# EVK-IRIS-W1-PIN-HEADERS_SDIO-HEADER.net
KiCad netlist of a schematic drawn in Altium Designer
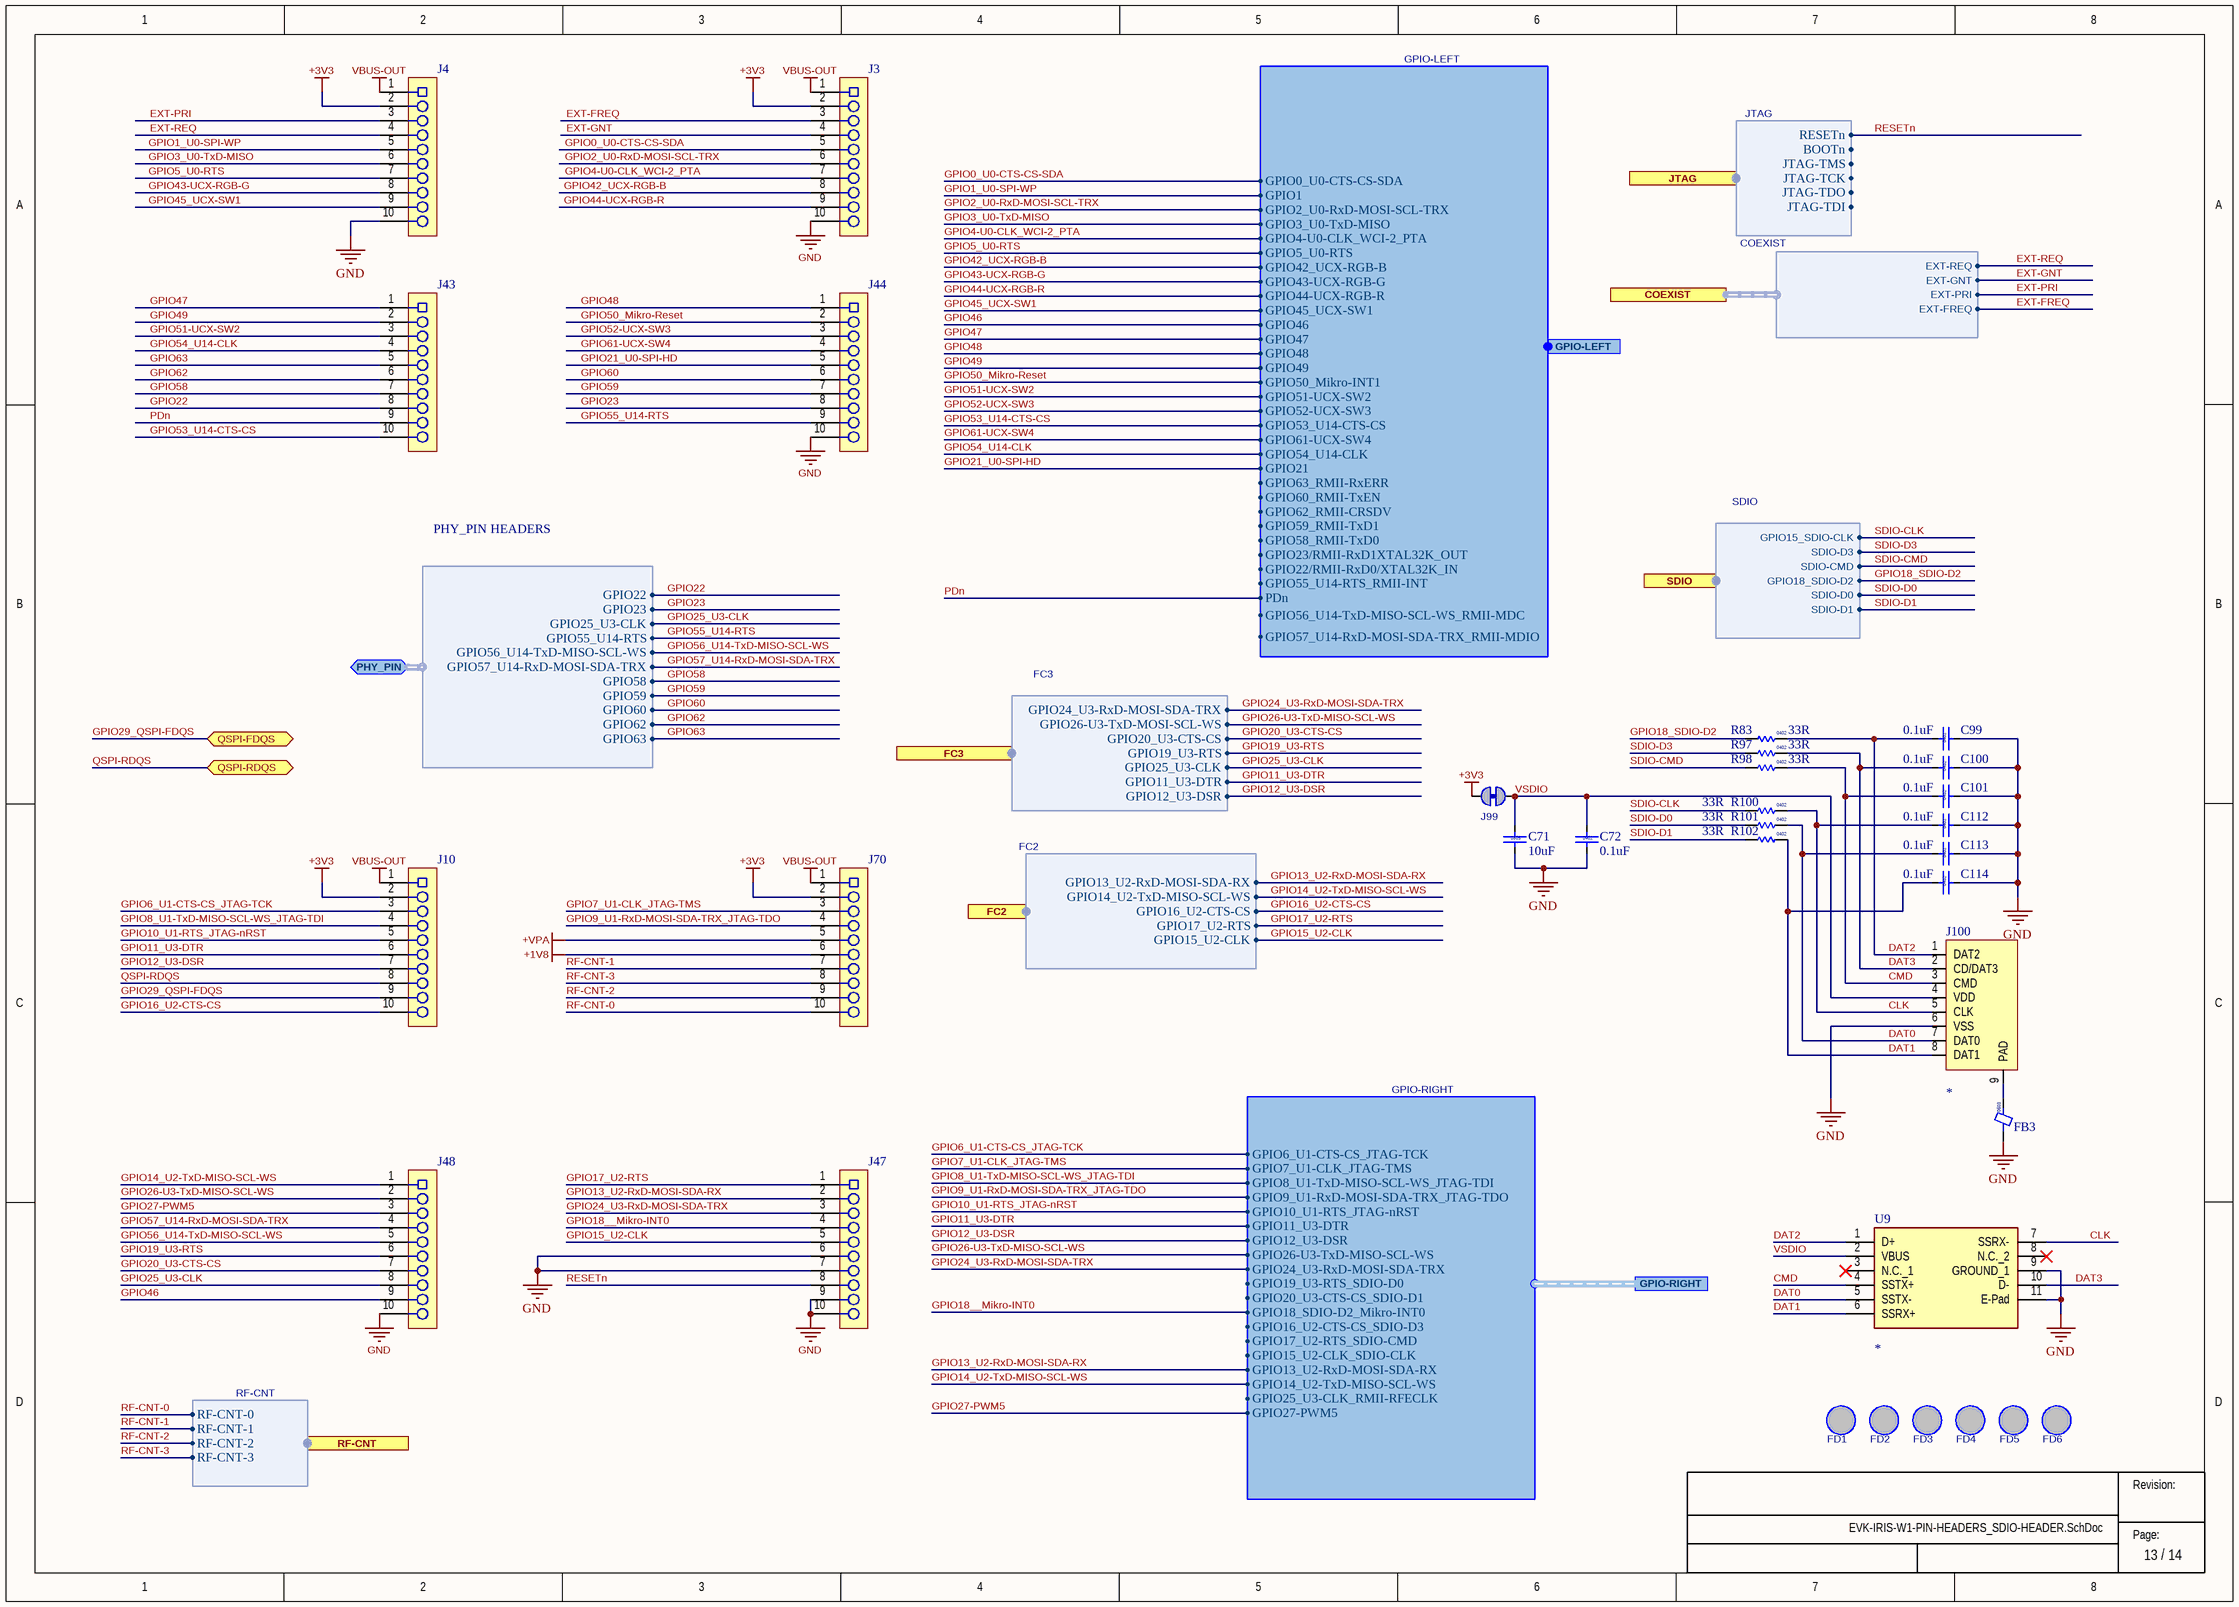
[diagram p0: EVK-IRIS-W1-PIN-HEADERS_SDIO-HEADER.SchDoc]

(export (version "E")
  (design (tool "Eeschema 10.0.6"))
  (components
    (comp (ref "C71")
      (value "10uF")
      (footprint "Cap 0805 HD")
      (description "Capacitor, Ceramic, 10uF 16V 10% X7R, 0805")
      (fields
        (field (name "SIZE") "0805")
        (field (name "PART NUMBER") "120-00133")
        (field (name "TOLERANCE") "+/- 10%")
      )
      (libsource (lib "Arena_Parts_DB_Lib") (part "Cap Chip"))
    )
    (comp (ref "C72")
      (value "0.1uF")
      (footprint "Cap 0402 HD")
      (description "Cap, Ceramic 0.1uF 16V 10% X7R 0402.")
      (fields
        (field (name "SIZE") "0402")
        (field (name "PART NUMBER") "120-00077")
        (field (name "TOLERANCE") "+/- 10%")
      )
      (libsource (lib "Arena_Parts_DB_Lib") (part "Cap Chip"))
    )
    (comp (ref "C99")
      (value "0.1uF")
      (footprint "Cap 0402 HD")
      (description "Cap, Ceramic 0.1uF 16V 10% X7R 0402.")
      (fields
        (field (name "SIZE") "0402")
        (field (name "PART NUMBER") "120-00077")
        (field (name "TOLERANCE") "+/- 10%")
      )
      (libsource (lib "Arena_Parts_DB_Lib") (part "Cap Chip"))
    )
    (comp (ref "C100")
      (value "0.1uF")
      (footprint "Cap 0402 HD")
      (description "Cap, Ceramic 0.1uF 16V 10% X7R 0402.")
      (fields
        (field (name "SIZE") "0402")
        (field (name "PART NUMBER") "120-00077")
        (field (name "TOLERANCE") "+/- 10%")
      )
      (libsource (lib "Arena_Parts_DB_Lib") (part "Cap Chip"))
    )
    (comp (ref "C101")
      (value "0.1uF")
      (footprint "Cap 0402 HD")
      (description "Cap, Ceramic 0.1uF 16V 10% X7R 0402.")
      (fields
        (field (name "SIZE") "0402")
        (field (name "PART NUMBER") "120-00077")
        (field (name "TOLERANCE") "+/- 10%")
      )
      (libsource (lib "Arena_Parts_DB_Lib") (part "Cap Chip"))
    )
    (comp (ref "C112")
      (value "0.1uF")
      (footprint "Cap 0402 HD")
      (description "Cap, Ceramic 0.1uF 16V 10% X7R 0402.")
      (fields
        (field (name "SIZE") "0402")
        (field (name "PART NUMBER") "120-00077")
        (field (name "TOLERANCE") "+/- 10%")
      )
      (libsource (lib "Arena_Parts_DB_Lib") (part "Cap Chip"))
    )
    (comp (ref "C113")
      (value "0.1uF")
      (footprint "Cap 0402 HD")
      (description "Cap, Ceramic 0.1uF 16V 10% X7R 0402.")
      (fields
        (field (name "SIZE") "0402")
        (field (name "PART NUMBER") "120-00077")
        (field (name "TOLERANCE") "+/- 10%")
      )
      (libsource (lib "Arena_Parts_DB_Lib") (part "Cap Chip"))
    )
    (comp (ref "C114")
      (value "0.1uF")
      (footprint "Cap 0402 HD")
      (description "Cap, Ceramic 0.1uF 16V 10% X7R 0402.")
      (fields
        (field (name "SIZE") "0402")
        (field (name "PART NUMBER") "120-00077")
        (field (name "TOLERANCE") "+/- 10%")
      )
      (libsource (lib "Arena_Parts_DB_Lib") (part "Cap Chip"))
    )
    (comp (ref "FB3")
      (value "BLM18EG221SN1")
      (footprint "BLM18EG221SN1")
      (description "Ferrite Bead, 220ohm @ 100MHz, 2A, 0603")
      (fields (field (name "VOLTAGE") "None") (field (name "SIZE") "0603"))
      (libsource (lib "BLM18EG221SN1") (part "BLM18EG221SN1"))
    )
    (comp (ref "FD1")
      (value "Fiducial_1mmDNP")
      (footprint "Fiducial 1mm - Circle")
      (description "1mm Fiducial Target")
      (fields (field (name "PART NUMBER") "Fiducial_1mm") (field (name "ADDED BY") "EMOO"))
      (libsource (lib "PCB_Misc") (part "Fiducial_1mm_Circle"))
    )
    (comp (ref "FD2")
      (value "Fiducial_1mmDNP")
      (footprint "Fiducial 1mm - Circle")
      (description "1mm Fiducial Target")
      (fields (field (name "PART NUMBER") "Fiducial_1mm") (field (name "ADDED BY") "EMOO"))
      (libsource (lib "PCB_Misc") (part "Fiducial_1mm_Circle"))
    )
    (comp (ref "FD3")
      (value "Fiducial_1mmDNP")
      (footprint "Fiducial 1mm - Circle")
      (description "1mm Fiducial Target")
      (fields (field (name "PART NUMBER") "Fiducial_1mm") (field (name "ADDED BY") "EMOO"))
      (libsource (lib "PCB_Misc") (part "Fiducial_1mm_Circle"))
    )
    (comp (ref "FD4")
      (value "Fiducial_1mmDNP")
      (footprint "Fiducial 1mm - Circle")
      (description "1mm Fiducial Target")
      (fields (field (name "PART NUMBER") "Fiducial_1mm") (field (name "ADDED BY") "EMOO"))
      (libsource (lib "PCB_Misc") (part "Fiducial_1mm_Circle"))
    )
    (comp (ref "FD5")
      (value "Fiducial_1mmDNP")
      (footprint "Fiducial 1mm - Circle")
      (description "1mm Fiducial Target")
      (fields (field (name "PART NUMBER") "Fiducial_1mm") (field (name "ADDED BY") "EMOO"))
      (libsource (lib "PCB_Misc") (part "Fiducial_1mm_Circle"))
    )
    (comp (ref "FD6")
      (value "Fiducial_1mmDNP")
      (footprint "Fiducial 1mm - Circle")
      (description "1mm Fiducial Target")
      (fields (field (name "PART NUMBER") "Fiducial_1mm") (field (name "ADDED BY") "EMOO"))
      (libsource (lib "PCB_Misc") (part "Fiducial_1mm_Circle"))
    )
    (comp (ref "J3")
      (value "130-00046")
      (footprint "HDR-0.1P-10PIN-10x1-TH")
      (description "Header, 0.100\" Pitch, 10Pin, 10x1, Through Hole")
      (fields (field (name "VOLTAGE") "None"))
      (libsource (lib "Arena_Parts_DB_Lib") (part "CON-10Pin_1Row"))
    )
    (comp (ref "J4")
      (value "130-00046")
      (footprint "HDR-0.1P-10PIN-10x1-TH")
      (description "Header, 0.100\" Pitch, 10Pin, 10x1, Through Hole")
      (fields (field (name "VOLTAGE") "None"))
      (libsource (lib "Arena_Parts_DB_Lib") (part "CON-10Pin_1Row"))
    )
    (comp (ref "J10")
      (value "130-00046")
      (footprint "HDR-0.1P-10PIN-10x1-TH")
      (description "Header, 0.100\" Pitch, 10Pin, 10x1, Through Hole")
      (fields (field (name "VOLTAGE") "None"))
      (libsource (lib "Arena_Parts_DB_Lib") (part "CON-10Pin_1Row"))
    )
    (comp (ref "J43")
      (value "130-00046")
      (footprint "HDR-0.1P-10PIN-10x1-TH")
      (description "Header, 0.100\" Pitch, 10Pin, 10x1, Through Hole")
      (fields (field (name "VOLTAGE") "None"))
      (libsource (lib "Arena_Parts_DB_Lib") (part "CON-10Pin_1Row"))
    )
    (comp (ref "J44")
      (value "130-00046")
      (footprint "HDR-0.1P-10PIN-10x1-TH")
      (description "Header, 0.100\" Pitch, 10Pin, 10x1, Through Hole")
      (fields (field (name "VOLTAGE") "None"))
      (libsource (lib "Arena_Parts_DB_Lib") (part "CON-10Pin_1Row"))
    )
    (comp (ref "J47")
      (value "130-00046")
      (footprint "HDR-0.1P-10PIN-10x1-TH")
      (description "Header, 0.100\" Pitch, 10Pin, 10x1, Through Hole")
      (fields (field (name "VOLTAGE") "None"))
      (libsource (lib "Arena_Parts_DB_Lib") (part "CON-10Pin_1Row"))
    )
    (comp (ref "J48")
      (value "130-00046")
      (footprint "HDR-0.1P-10PIN-10x1-TH")
      (description "Header, 0.100\" Pitch, 10Pin, 10x1, Through Hole")
      (fields (field (name "VOLTAGE") "None"))
      (libsource (lib "Arena_Parts_DB_Lib") (part "CON-10Pin_1Row"))
    )
    (comp (ref "J70")
      (value "130-00046")
      (footprint "HDR-0.1P-10PIN-10x1-TH")
      (description "Header, 0.100\" Pitch, 10Pin, 10x1, Through Hole")
      (fields (field (name "VOLTAGE") "None"))
      (libsource (lib "Arena_Parts_DB_Lib") (part "CON-10Pin_1Row"))
    )
    (comp (ref "J99")
      (value "Solderbridge-ShortDNP")
      (footprint "Solderbridge-Short")
      (description "Solderbridge-Short")
      (fields (field (name "ADDED BY") "Paul B"))
      (libsource (lib "PCB_Misc") (part "Solderbridge-Short"))
    )
    (comp (ref "J100")
      (value "130-00062")
      (footprint "Micro_SD_SKT_SMT_RA")
      (description "Micro SD Card Socket, Right Angle, with 4 Ground Pads, SMT")
      (fields (field (name "MANUFACTURER P/N") "*") (field (name "VOLTAGE") "None"))
      (libsource (lib "Arena_Parts_DB_Lib") (part "SD_Card_SKT"))
    )
    (comp (ref "R83")
      (value "33R")
      (footprint "RES 0402 HD")
      (description "RES THICK FILM CHIP 0402 33R 5% 50V 63mW")
      (fields
        (field (name "SIZE") "0402")
        (field (name "PART NUMBER") "UBXH18-0008013")
        (field (name "TOLERANCE") "5%")
        (field (name "EDITOR") "matej.budin")
        (field (name "RELEASED BY") "erian.bezhani")
      )
      (libsource (lib "UBX_Parts_DB_Lib") (part "Res sm"))
    )
    (comp (ref "R97")
      (value "33R")
      (footprint "RES 0402 HD")
      (description "RES THICK FILM CHIP 0402 33R 5% 50V 63mW")
      (fields
        (field (name "SIZE") "0402")
        (field (name "PART NUMBER") "UBXH18-0008013")
        (field (name "TOLERANCE") "5%")
        (field (name "EDITOR") "matej.budin")
        (field (name "RELEASED BY") "erian.bezhani")
      )
      (libsource (lib "UBX_Parts_DB_Lib") (part "Res sm"))
    )
    (comp (ref "R98")
      (value "33R")
      (footprint "RES 0402 HD")
      (description "RES THICK FILM CHIP 0402 33R 5% 50V 63mW")
      (fields
        (field (name "SIZE") "0402")
        (field (name "PART NUMBER") "UBXH18-0008013")
        (field (name "TOLERANCE") "5%")
        (field (name "EDITOR") "matej.budin")
        (field (name "RELEASED BY") "erian.bezhani")
      )
      (libsource (lib "UBX_Parts_DB_Lib") (part "Res sm"))
    )
    (comp (ref "R100")
      (value "33R")
      (footprint "RES 0402 HD")
      (description "RES THICK FILM CHIP 0402 33R 5% 50V 63mW")
      (fields
        (field (name "SIZE") "0402")
        (field (name "PART NUMBER") "UBXH18-0008013")
        (field (name "TOLERANCE") "5%")
        (field (name "EDITOR") "matej.budin")
        (field (name "RELEASED BY") "erian.bezhani")
      )
      (libsource (lib "UBX_Parts_DB_Lib") (part "Res sm"))
    )
    (comp (ref "R101")
      (value "33R")
      (footprint "RES 0402 HD")
      (description "RES THICK FILM CHIP 0402 33R 5% 50V 63mW")
      (fields
        (field (name "SIZE") "0402")
        (field (name "PART NUMBER") "UBXH18-0008013")
        (field (name "TOLERANCE") "5%")
        (field (name "EDITOR") "matej.budin")
        (field (name "RELEASED BY") "erian.bezhani")
      )
      (libsource (lib "UBX_Parts_DB_Lib") (part "Res sm"))
    )
    (comp (ref "R102")
      (value "33R")
      (footprint "RES 0402 HD")
      (description "RES THICK FILM CHIP 0402 33R 5% 50V 63mW")
      (fields
        (field (name "SIZE") "0402")
        (field (name "PART NUMBER") "UBXH18-0008013")
        (field (name "TOLERANCE") "5%")
        (field (name "EDITOR") "matej.budin")
        (field (name "RELEASED BY") "erian.bezhani")
      )
      (libsource (lib "UBX_Parts_DB_Lib") (part "Res sm"))
    )
    (comp (ref "U9")
      (value "~")
      (footprint "DFN10")
      (description "4.5V, 7.2V Clamp 4A (8/20µs) Ipp Tvs Diode Surface Mount 10-DFN (4.1x2)")
      (fields (field (name "MANUFACTURER P/N") "*"))
      (libsource (lib "CDDFN10-0516P") (part "CDDFN10-0516P"))
    )
  )
  (nets
    (net (code "11") (name "+1V8") (class "Default") (node (ref "J70") (pin "6") (pintype "passive")))
    (net (code "12") (name "+3V3") (class "Default")
      (node (ref "J10") (pin "2") (pintype "passive"))
      (node (ref "J3") (pin "2") (pintype "passive"))
      (node (ref "J4") (pin "2") (pintype "passive"))
      (node (ref "J70") (pin "2") (pintype "passive"))
      (node (ref "J99") (pin "1") (pinfunction "1_1") (pintype "passive"))
    )
    (net (code "13") (name "+VPA") (class "Default") (node (ref "J70") (pin "5") (pintype "passive")))
    (net (code "14") (name "/CLK") (class "Default")
      (node (ref "C112") (pin "1") (pinfunction "1_1") (pintype "passive"))
      (node (ref "J100") (pin "5") (pinfunction "CLK_5") (pintype "passive"))
      (node (ref "R100") (pin "2") (pinfunction "2_2") (pintype "passive"))
      (node (ref "U9") (pin "7") (pinfunction "SSRX-_7") (pintype "passive"))
    )
    (net (code "15") (name "/CMD") (class "Default")
      (node (ref "C101") (pin "1") (pinfunction "1_1") (pintype "passive"))
      (node (ref "J100") (pin "3") (pinfunction "CMD_3") (pintype "passive"))
      (node (ref "R98") (pin "2") (pinfunction "2_2") (pintype "passive"))
      (node (ref "U9") (pin "4") (pinfunction "SSTX+_4") (pintype "passive"))
    )
    (net (code "16") (name "/DAT0") (class "Default")
      (node (ref "C113") (pin "1") (pinfunction "1_1") (pintype "passive"))
      (node (ref "J100") (pin "7") (pinfunction "DAT0_7") (pintype "passive"))
      (node (ref "R101") (pin "2") (pinfunction "2_2") (pintype "passive"))
      (node (ref "U9") (pin "5") (pinfunction "SSTX-_5") (pintype "passive"))
    )
    (net (code "17") (name "/DAT1") (class "Default")
      (node (ref "C114") (pin "1") (pinfunction "1_1") (pintype "passive"))
      (node (ref "J100") (pin "8") (pinfunction "DAT1_8") (pintype "passive"))
      (node (ref "R102") (pin "2") (pinfunction "2_2") (pintype "passive"))
      (node (ref "U9") (pin "6") (pinfunction "SSRX+_6") (pintype "passive"))
    )
    (net (code "18") (name "/DAT2") (class "Default")
      (node (ref "C99") (pin "1") (pinfunction "1_1") (pintype "passive"))
      (node (ref "J100") (pin "1") (pinfunction "DAT2_1") (pintype "passive"))
      (node (ref "R83") (pin "2") (pinfunction "2_2") (pintype "passive"))
      (node (ref "U9") (pin "1") (pinfunction "D+_1") (pintype "passive"))
    )
    (net (code "19") (name "/DAT3") (class "Default")
      (node (ref "C100") (pin "1") (pinfunction "1_1") (pintype "passive"))
      (node (ref "J100") (pin "2") (pinfunction "CD/DAT3_2") (pintype "passive"))
      (node (ref "R97") (pin "2") (pinfunction "2_2") (pintype "passive"))
      (node (ref "U9") (pin "10") (pinfunction "D-_10") (pintype "passive"))
    )
    (net (code "20") (name "/EXT-FREQ") (class "Default") (node (ref "J3") (pin "3") (pintype "passive")))
    (net (code "21") (name "/EXT-GNT") (class "Default") (node (ref "J3") (pin "4") (pintype "passive")))
    (net (code "22") (name "/EXT-PRI") (class "Default") (node (ref "J4") (pin "3") (pintype "passive")))
    (net (code "23") (name "/EXT-REQ") (class "Default") (node (ref "J4") (pin "4") (pintype "passive")))
    (net (code "24") (name "/GPIO0_U0-CTS-CS-SDA") (class "Default")
      (node (ref "J3") (pin "5") (pintype "passive"))
    )
    (net (code "25") (name "/GPIO1_U0-SPI-WP") (class "Default")
      (node (ref "J4") (pin "5") (pintype "passive"))
    )
    (net (code "26") (name "/GPIO2_U0-RxD-MOSI-SCL-TRX") (class "Default")
      (node (ref "J3") (pin "6") (pintype "passive"))
    )
    (net (code "27") (name "/GPIO3_U0-TxD-MISO") (class "Default")
      (node (ref "J4") (pin "6") (pintype "passive"))
    )
    (net (code "28") (name "/GPIO4-U0-CLK_WCI-2_PTA") (class "Default")
      (node (ref "J3") (pin "7") (pintype "passive"))
    )
    (net (code "29") (name "/GPIO5_U0-RTS") (class "Default") (node (ref "J4") (pin "7") (pintype "passive")))
    (net (code "30") (name "/GPIO6_U1-CTS-CS_JTAG-TCK") (class "Default")
      (node (ref "J10") (pin "3") (pintype "passive"))
    )
    (net (code "31") (name "/GPIO7_U1-CLK_JTAG-TMS") (class "Default")
      (node (ref "J70") (pin "3") (pintype "passive"))
    )
    (net (code "32") (name "/GPIO8_U1-TxD-MISO-SCL-WS_JTAG-TDI") (class "Default")
      (node (ref "J10") (pin "4") (pintype "passive"))
    )
    (net (code "33") (name "/GPIO9_U1-RxD-MOSI-SDA-TRX_JTAG-TDO") (class "Default")
      (node (ref "J70") (pin "4") (pintype "passive"))
    )
    (net (code "34") (name "/GPIO10_U1-RTS_JTAG-nRST") (class "Default")
      (node (ref "J10") (pin "5") (pintype "passive"))
    )
    (net (code "35") (name "/GPIO11_U3-DTR") (class "Default")
      (node (ref "J10") (pin "6") (pintype "passive"))
    )
    (net (code "36") (name "/GPIO12_U3-DSR") (class "Default")
      (node (ref "J10") (pin "7") (pintype "passive"))
    )
    (net (code "37") (name "/GPIO13_U2-RxD-MOSI-SDA-RX") (class "Default")
      (node (ref "J47") (pin "2") (pintype "passive"))
    )
    (net (code "38") (name "/GPIO14_U2-TxD-MISO-SCL-WS") (class "Default")
      (node (ref "J48") (pin "1") (pintype "passive"))
    )
    (net (code "39") (name "/GPIO15_U2-CLK") (class "Default")
      (node (ref "J47") (pin "5") (pintype "passive"))
    )
    (net (code "40") (name "/GPIO16_U2-CTS-CS") (class "Default")
      (node (ref "J10") (pin "10") (pintype "passive"))
    )
    (net (code "41") (name "/GPIO17_U2-RTS") (class "Default")
      (node (ref "J47") (pin "1") (pintype "passive"))
    )
    (net (code "42") (name "/GPIO18_SDIO-D2") (class "Default")
      (node (ref "R83") (pin "1") (pinfunction "1_1") (pintype "passive"))
    )
    (net (code "43") (name "/GPIO18__Mikro-INT0") (class "Default")
      (node (ref "J47") (pin "4") (pintype "passive"))
    )
    (net (code "44") (name "/GPIO19_U3-RTS") (class "Default")
      (node (ref "J48") (pin "6") (pintype "passive"))
    )
    (net (code "45") (name "/GPIO20_U3-CTS-CS") (class "Default")
      (node (ref "J48") (pin "7") (pintype "passive"))
    )
    (net (code "46") (name "/GPIO21_U0-SPI-HD") (class "Default")
      (node (ref "J44") (pin "5") (pintype "passive"))
    )
    (net (code "47") (name "/GPIO22") (class "Default") (node (ref "J43") (pin "8") (pintype "passive")))
    (net (code "48") (name "/GPIO23") (class "Default") (node (ref "J44") (pin "8") (pintype "passive")))
    (net (code "49") (name "/GPIO24_U3-RxD-MOSI-SDA-TRX") (class "Default")
      (node (ref "J47") (pin "3") (pintype "passive"))
    )
    (net (code "50") (name "/GPIO25_U3-CLK") (class "Default")
      (node (ref "J48") (pin "8") (pintype "passive"))
    )
    (net (code "51") (name "/GPIO26-U3-TxD-MISO-SCL-WS") (class "Default")
      (node (ref "J48") (pin "2") (pintype "passive"))
    )
    (net (code "52") (name "/GPIO27-PWM5") (class "Default") (node (ref "J48") (pin "3") (pintype "passive")))
    (net (code "53") (name "/GPIO29_QSPI-FDQS") (class "Default")
      (node (ref "J10") (pin "9") (pintype "passive"))
    )
    (net (code "54") (name "/GPIO42_UCX-RGB-B") (class "Default")
      (node (ref "J3") (pin "8") (pintype "passive"))
    )
    (net (code "55") (name "/GPIO43-UCX-RGB-G") (class "Default")
      (node (ref "J4") (pin "8") (pintype "passive"))
    )
    (net (code "56") (name "/GPIO44-UCX-RGB-R") (class "Default")
      (node (ref "J3") (pin "9") (pintype "passive"))
    )
    (net (code "57") (name "/GPIO45_UCX-SW1") (class "Default")
      (node (ref "J4") (pin "9") (pintype "passive"))
    )
    (net (code "58") (name "/GPIO46") (class "Default") (node (ref "J48") (pin "9") (pintype "passive")))
    (net (code "59") (name "/GPIO47") (class "Default") (node (ref "J43") (pin "1") (pintype "passive")))
    (net (code "60") (name "/GPIO48") (class "Default") (node (ref "J44") (pin "1") (pintype "passive")))
    (net (code "61") (name "/GPIO49") (class "Default") (node (ref "J43") (pin "2") (pintype "passive")))
    (net (code "62") (name "/GPIO50_Mikro-Reset") (class "Default")
      (node (ref "J44") (pin "2") (pintype "passive"))
    )
    (net (code "63") (name "/GPIO51-UCX-SW2") (class "Default")
      (node (ref "J43") (pin "3") (pintype "passive"))
    )
    (net (code "64") (name "/GPIO52-UCX-SW3") (class "Default")
      (node (ref "J44") (pin "3") (pintype "passive"))
    )
    (net (code "65") (name "/GPIO53_U14-CTS-CS") (class "Default")
      (node (ref "J43") (pin "10") (pintype "passive"))
    )
    (net (code "66") (name "/GPIO54_U14-CLK") (class "Default")
      (node (ref "J43") (pin "4") (pintype "passive"))
    )
    (net (code "67") (name "/GPIO55_U14-RTS") (class "Default")
      (node (ref "J44") (pin "9") (pintype "passive"))
    )
    (net (code "68") (name "/GPIO56_U14-TxD-MISO-SCL-WS") (class "Default")
      (node (ref "J48") (pin "5") (pintype "passive"))
    )
    (net (code "69") (name "/GPIO57_U14-RxD-MOSI-SDA-TRX") (class "Default")
      (node (ref "J48") (pin "4") (pintype "passive"))
    )
    (net (code "70") (name "/GPIO58") (class "Default") (node (ref "J43") (pin "7") (pintype "passive")))
    (net (code "71") (name "/GPIO59") (class "Default") (node (ref "J44") (pin "7") (pintype "passive")))
    (net (code "72") (name "/GPIO60") (class "Default") (node (ref "J44") (pin "6") (pintype "passive")))
    (net (code "73") (name "/GPIO61-UCX-SW4") (class "Default")
      (node (ref "J44") (pin "4") (pintype "passive"))
    )
    (net (code "74") (name "/GPIO62") (class "Default") (node (ref "J43") (pin "6") (pintype "passive")))
    (net (code "75") (name "/GPIO63") (class "Default") (node (ref "J43") (pin "5") (pintype "passive")))
    (net (code "76") (name "/PDn") (class "Default") (node (ref "J43") (pin "9") (pintype "passive")))
    (net (code "77") (name "/QSPI-RDQS") (class "Default") (node (ref "J10") (pin "8") (pintype "passive")))
    (net (code "78") (name "/RESETn") (class "Default") (node (ref "J47") (pin "8") (pintype "passive")))
    (net (code "79") (name "/RF-CNT-0") (class "Default") (node (ref "J70") (pin "10") (pintype "passive")))
    (net (code "80") (name "/RF-CNT-1") (class "Default") (node (ref "J70") (pin "7") (pintype "passive")))
    (net (code "81") (name "/RF-CNT-2") (class "Default") (node (ref "J70") (pin "9") (pintype "passive")))
    (net (code "82") (name "/RF-CNT-3") (class "Default") (node (ref "J70") (pin "8") (pintype "passive")))
    (net (code "83") (name "/SDIO-CLK") (class "Default")
      (node (ref "R100") (pin "1") (pinfunction "1_1") (pintype "passive"))
    )
    (net (code "84") (name "/SDIO-CMD") (class "Default")
      (node (ref "R98") (pin "1") (pinfunction "1_1") (pintype "passive"))
    )
    (net (code "85") (name "/SDIO-D0") (class "Default")
      (node (ref "R101") (pin "1") (pinfunction "1_1") (pintype "passive"))
    )
    (net (code "86") (name "/SDIO-D1") (class "Default")
      (node (ref "R102") (pin "1") (pinfunction "1_1") (pintype "passive"))
    )
    (net (code "87") (name "/SDIO-D3") (class "Default")
      (node (ref "R97") (pin "1") (pinfunction "1_1") (pintype "passive"))
    )
    (net (code "88") (name "/VSDIO") (class "Default")
      (node (ref "C71") (pin "1") (pinfunction "1_1") (pintype "passive"))
      (node (ref "C72") (pin "1") (pinfunction "1_1") (pintype "passive"))
      (node (ref "J100") (pin "4") (pinfunction "VDD_4") (pintype "power_in"))
      (node (ref "J99") (pin "2") (pinfunction "2_2") (pintype "passive"))
      (node (ref "U9") (pin "2") (pinfunction "VBUS_2") (pintype "passive"))
    )
    (net (code "98") (name "GND") (class "Default")
      (node (ref "C100") (pin "2") (pinfunction "2_2") (pintype "passive"))
      (node (ref "C101") (pin "2") (pinfunction "2_2") (pintype "passive"))
      (node (ref "C112") (pin "2") (pinfunction "2_2") (pintype "passive"))
      (node (ref "C113") (pin "2") (pinfunction "2_2") (pintype "passive"))
      (node (ref "C114") (pin "2") (pinfunction "2_2") (pintype "passive"))
      (node (ref "C71") (pin "2") (pinfunction "2_2") (pintype "passive"))
      (node (ref "C72") (pin "2") (pinfunction "2_2") (pintype "passive"))
      (node (ref "C99") (pin "2") (pinfunction "2_2") (pintype "passive"))
      (node (ref "FB3") (pin "1") (pinfunction "1_1") (pintype "passive"))
      (node (ref "J100") (pin "6") (pinfunction "VSS_6") (pintype "power_in"))
      (node (ref "J3") (pin "10") (pintype "passive"))
      (node (ref "J4") (pin "10") (pintype "passive"))
      (node (ref "J44") (pin "10") (pintype "passive"))
      (node (ref "J47") (pin "10") (pintype "passive"))
      (node (ref "J47") (pin "6") (pintype "passive"))
      (node (ref "J47") (pin "7") (pintype "passive"))
      (node (ref "J47") (pin "9") (pintype "passive"))
      (node (ref "J48") (pin "10") (pintype "passive"))
      (node (ref "U9") (pin "11") (pinfunction "E-Pad_11") (pintype "passive"))
      (node (ref "U9") (pin "9") (pinfunction "GROUND_1_9") (pintype "passive"))
    )
    (net (code "99") (name "Net-(J100-PAD)") (class "Default")
      (node (ref "FB3") (pin "2") (pinfunction "2_2") (pintype "passive"))
      (node (ref "J100") (pin "9") (pinfunction "PAD_9") (pintype "power_in"))
    )
    (net (code "100") (name "VBUS-OUT") (class "Default")
      (node (ref "J10") (pin "1") (pintype "passive"))
      (node (ref "J3") (pin "1") (pintype "passive"))
      (node (ref "J4") (pin "1") (pintype "passive"))
      (node (ref "J70") (pin "1") (pintype "passive"))
    )
    (net (code "101") (name "unconnected-(U9-N.C._1-Pad3)") (class "Default")
      (node (ref "U9") (pin "3") (pinfunction "N.C._1_3") (pintype "passive+no_connect"))
    )
    (net (code "102") (name "unconnected-(U9-N.C._2-Pad8)") (class "Default")
      (node (ref "U9") (pin "8") (pinfunction "N.C._2_8") (pintype "passive+no_connect"))
    )
  )
)
